# Bluetooth_BM20_Breakout.net
KiCad netlist of a schematic drawn in EAGLE
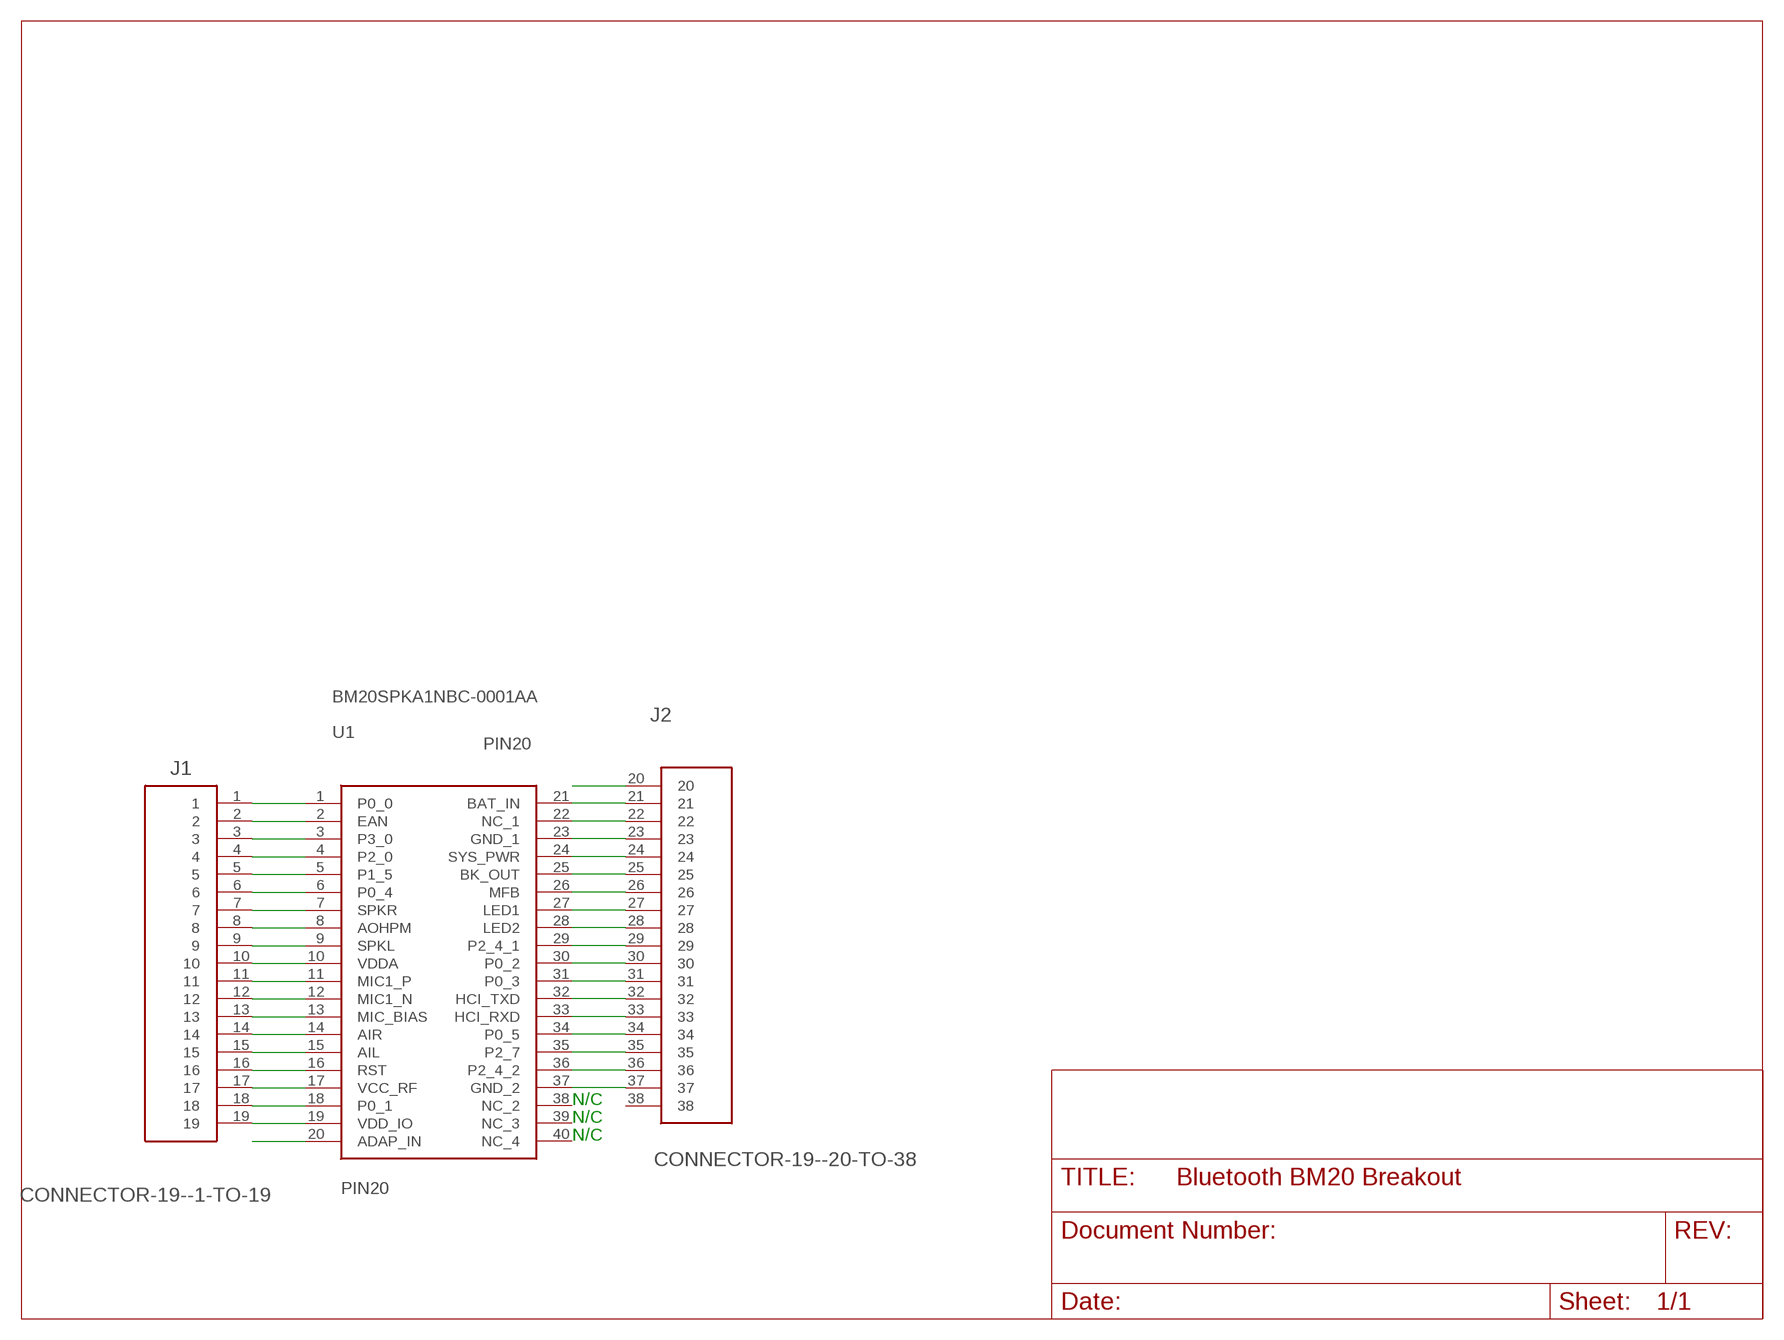
[diagram p0: schematic, sheet 1]

(export (version "E")
  (design (tool "Eeschema 10.0.6"))
  (components
    (comp (ref "J1")
      (value "CONNECTOR-19--1-TO-19")
      (footprint "eagle-import:ESQ-119-XX-XX-S")
      (libsource (lib "eagle-import") (part "CONNECTOR-19--1-TO-19"))
    )
    (comp (ref "J2")
      (value "CONNECTOR-19--20-TO-38")
      (footprint "eagle-import:ESQ-119-XX-XX-S--PIN-1-ROUND")
      (libsource (lib "eagle-import") (part "CONNECTOR-19--20-TO-38"))
    )
    (comp (ref "U1")
      (value "BM20SPKA1NBC-0001AA")
      (footprint "eagle-import:BM20SPKA1NBC0001AA")
      (fields (field (name "MOUSER_PART_NUMBER") "579-SPKA1NBC-0001AA"))
      (libsource (lib "eagle-import") (part "BM20SPKA1NBC-0001AA"))
    )
  )
  (nets
    (net (code "1") (name "/PIN20") (class "Default")
      (node (ref "J2") (pin "20") (pinfunction "20_20") (pintype "bidirectional"))
      (node (ref "U1") (pin "20") (pinfunction "ADAP_IN_20") (pintype "bidirectional"))
    )
    (net (code "2") (name "Net-(U1-AIL)") (class "Default")
      (node (ref "J1") (pin "15") (pinfunction "15_15") (pintype "bidirectional"))
      (node (ref "U1") (pin "15") (pinfunction "AIL_15") (pintype "bidirectional"))
    )
    (net (code "3") (name "Net-(U1-AIR)") (class "Default")
      (node (ref "J1") (pin "14") (pinfunction "14_14") (pintype "bidirectional"))
      (node (ref "U1") (pin "14") (pinfunction "AIR_14") (pintype "bidirectional"))
    )
    (net (code "4") (name "Net-(U1-AOHPM)") (class "Default")
      (node (ref "J1") (pin "8") (pinfunction "8_8") (pintype "bidirectional"))
      (node (ref "U1") (pin "8") (pinfunction "AOHPM_8") (pintype "bidirectional"))
    )
    (net (code "5") (name "Net-(U1-BAT_IN)") (class "Default")
      (node (ref "J2") (pin "21") (pinfunction "21_21") (pintype "bidirectional"))
      (node (ref "U1") (pin "21") (pinfunction "BAT_IN_21") (pintype "bidirectional"))
    )
    (net (code "6") (name "Net-(U1-BK_OUT)") (class "Default")
      (node (ref "J2") (pin "25") (pinfunction "25_25") (pintype "bidirectional"))
      (node (ref "U1") (pin "25") (pinfunction "BK_OUT_25") (pintype "bidirectional"))
    )
    (net (code "7") (name "Net-(U1-EAN)") (class "Default")
      (node (ref "J1") (pin "2") (pinfunction "2_2") (pintype "bidirectional"))
      (node (ref "U1") (pin "2") (pinfunction "EAN_2") (pintype "bidirectional"))
    )
    (net (code "8") (name "Net-(U1-GND_1)") (class "Default")
      (node (ref "J2") (pin "23") (pinfunction "23_23") (pintype "bidirectional"))
      (node (ref "U1") (pin "23") (pinfunction "GND_1_23") (pintype "bidirectional"))
    )
    (net (code "9") (name "Net-(U1-GND_2)") (class "Default")
      (node (ref "J2") (pin "37") (pinfunction "37_37") (pintype "bidirectional"))
      (node (ref "U1") (pin "37") (pinfunction "GND_2_37") (pintype "bidirectional"))
    )
    (net (code "10") (name "Net-(U1-HCI_RXD)") (class "Default")
      (node (ref "J2") (pin "33") (pinfunction "33_33") (pintype "bidirectional"))
      (node (ref "U1") (pin "33") (pinfunction "HCI_RXD_33") (pintype "bidirectional"))
    )
    (net (code "11") (name "Net-(U1-HCI_TXD)") (class "Default")
      (node (ref "J2") (pin "32") (pinfunction "32_32") (pintype "bidirectional"))
      (node (ref "U1") (pin "32") (pinfunction "HCI_TXD_32") (pintype "bidirectional"))
    )
    (net (code "12") (name "Net-(U1-LED1)") (class "Default")
      (node (ref "J2") (pin "27") (pinfunction "27_27") (pintype "bidirectional"))
      (node (ref "U1") (pin "27") (pinfunction "LED1_27") (pintype "bidirectional"))
    )
    (net (code "13") (name "Net-(U1-LED2)") (class "Default")
      (node (ref "J2") (pin "28") (pinfunction "28_28") (pintype "bidirectional"))
      (node (ref "U1") (pin "28") (pinfunction "LED2_28") (pintype "bidirectional"))
    )
    (net (code "14") (name "Net-(U1-MFB)") (class "Default")
      (node (ref "J2") (pin "26") (pinfunction "26_26") (pintype "bidirectional"))
      (node (ref "U1") (pin "26") (pinfunction "MFB_26") (pintype "bidirectional"))
    )
    (net (code "15") (name "Net-(U1-MIC1_N)") (class "Default")
      (node (ref "J1") (pin "12") (pinfunction "12_12") (pintype "bidirectional"))
      (node (ref "U1") (pin "12") (pinfunction "MIC1_N_12") (pintype "bidirectional"))
    )
    (net (code "16") (name "Net-(U1-MIC1_P)") (class "Default")
      (node (ref "J1") (pin "11") (pinfunction "11_11") (pintype "bidirectional"))
      (node (ref "U1") (pin "11") (pinfunction "MIC1_P_11") (pintype "bidirectional"))
    )
    (net (code "17") (name "Net-(U1-MIC_BIAS)") (class "Default")
      (node (ref "J1") (pin "13") (pinfunction "13_13") (pintype "bidirectional"))
      (node (ref "U1") (pin "13") (pinfunction "MIC_BIAS_13") (pintype "bidirectional"))
    )
    (net (code "18") (name "Net-(U1-NC_1)") (class "Default")
      (node (ref "J2") (pin "22") (pinfunction "22_22") (pintype "bidirectional"))
      (node (ref "U1") (pin "22") (pinfunction "NC_1_22") (pintype "bidirectional"))
    )
    (net (code "19") (name "Net-(U1-P0_0)") (class "Default")
      (node (ref "J1") (pin "1") (pinfunction "1_1") (pintype "bidirectional"))
      (node (ref "U1") (pin "1") (pinfunction "P0_0_1") (pintype "bidirectional"))
    )
    (net (code "20") (name "Net-(U1-P0_1)") (class "Default")
      (node (ref "J1") (pin "18") (pinfunction "18_18") (pintype "bidirectional"))
      (node (ref "U1") (pin "18") (pinfunction "P0_1_18") (pintype "bidirectional"))
    )
    (net (code "21") (name "Net-(U1-P0_2)") (class "Default")
      (node (ref "J2") (pin "30") (pinfunction "30_30") (pintype "bidirectional"))
      (node (ref "U1") (pin "30") (pinfunction "P0_2_30") (pintype "bidirectional"))
    )
    (net (code "22") (name "Net-(U1-P0_3)") (class "Default")
      (node (ref "J2") (pin "31") (pinfunction "31_31") (pintype "bidirectional"))
      (node (ref "U1") (pin "31") (pinfunction "P0_3_31") (pintype "bidirectional"))
    )
    (net (code "23") (name "Net-(U1-P0_4)") (class "Default")
      (node (ref "J1") (pin "6") (pinfunction "6_6") (pintype "bidirectional"))
      (node (ref "U1") (pin "6") (pinfunction "P0_4_6") (pintype "bidirectional"))
    )
    (net (code "24") (name "Net-(U1-P0_5)") (class "Default")
      (node (ref "J2") (pin "34") (pinfunction "34_34") (pintype "bidirectional"))
      (node (ref "U1") (pin "34") (pinfunction "P0_5_34") (pintype "bidirectional"))
    )
    (net (code "25") (name "Net-(U1-P1_5)") (class "Default")
      (node (ref "J1") (pin "5") (pinfunction "5_5") (pintype "bidirectional"))
      (node (ref "U1") (pin "5") (pinfunction "P1_5_5") (pintype "bidirectional"))
    )
    (net (code "26") (name "Net-(U1-P2_0)") (class "Default")
      (node (ref "J1") (pin "4") (pinfunction "4_4") (pintype "bidirectional"))
      (node (ref "U1") (pin "4") (pinfunction "P2_0_4") (pintype "bidirectional"))
    )
    (net (code "27") (name "Net-(U1-P2_4_1)") (class "Default")
      (node (ref "J2") (pin "29") (pinfunction "29_29") (pintype "bidirectional"))
      (node (ref "U1") (pin "29") (pinfunction "P2_4_1_29") (pintype "bidirectional"))
    )
    (net (code "28") (name "Net-(U1-P2_4_2)") (class "Default")
      (node (ref "J2") (pin "36") (pinfunction "36_36") (pintype "bidirectional"))
      (node (ref "U1") (pin "36") (pinfunction "P2_4_2_36") (pintype "bidirectional"))
    )
    (net (code "29") (name "Net-(U1-P2_7)") (class "Default")
      (node (ref "J2") (pin "35") (pinfunction "35_35") (pintype "bidirectional"))
      (node (ref "U1") (pin "35") (pinfunction "P2_7_35") (pintype "bidirectional"))
    )
    (net (code "30") (name "Net-(U1-P3_0)") (class "Default")
      (node (ref "J1") (pin "3") (pinfunction "3_3") (pintype "bidirectional"))
      (node (ref "U1") (pin "3") (pinfunction "P3_0_3") (pintype "bidirectional"))
    )
    (net (code "31") (name "Net-(U1-RST)") (class "Default")
      (node (ref "J1") (pin "16") (pinfunction "16_16") (pintype "bidirectional"))
      (node (ref "U1") (pin "16") (pinfunction "RST_16") (pintype "bidirectional"))
    )
    (net (code "32") (name "Net-(U1-SPKL)") (class "Default")
      (node (ref "J1") (pin "9") (pinfunction "9_9") (pintype "bidirectional"))
      (node (ref "U1") (pin "9") (pinfunction "SPKL_9") (pintype "bidirectional"))
    )
    (net (code "33") (name "Net-(U1-SPKR)") (class "Default")
      (node (ref "J1") (pin "7") (pinfunction "7_7") (pintype "bidirectional"))
      (node (ref "U1") (pin "7") (pinfunction "SPKR_7") (pintype "bidirectional"))
    )
    (net (code "34") (name "Net-(U1-SYS_PWR)") (class "Default")
      (node (ref "J2") (pin "24") (pinfunction "24_24") (pintype "bidirectional"))
      (node (ref "U1") (pin "24") (pinfunction "SYS_PWR_24") (pintype "bidirectional"))
    )
    (net (code "35") (name "Net-(U1-VCC_RF)") (class "Default")
      (node (ref "J1") (pin "17") (pinfunction "17_17") (pintype "bidirectional"))
      (node (ref "U1") (pin "17") (pinfunction "VCC_RF_17") (pintype "bidirectional"))
    )
    (net (code "36") (name "Net-(U1-VDDA)") (class "Default")
      (node (ref "J1") (pin "10") (pinfunction "10_10") (pintype "bidirectional"))
      (node (ref "U1") (pin "10") (pinfunction "VDDA_10") (pintype "bidirectional"))
    )
    (net (code "37") (name "Net-(U1-VDD_IO)") (class "Default")
      (node (ref "J1") (pin "19") (pinfunction "19_19") (pintype "bidirectional"))
      (node (ref "U1") (pin "19") (pinfunction "VDD_IO_19") (pintype "bidirectional"))
    )
    (net (code "38") (name "unconnected-(J2-Pad38)") (class "Default")
      (node (ref "J2") (pin "38") (pinfunction "38_38") (pintype "bidirectional"))
    )
    (net (code "39") (name "unconnected-(U1-NC_2-Pad38)") (class "Default")
      (node (ref "U1") (pin "38") (pinfunction "NC_2_38") (pintype "bidirectional"))
    )
    (net (code "40") (name "unconnected-(U1-NC_3-Pad39)") (class "Default")
      (node (ref "U1") (pin "39") (pinfunction "NC_3_39") (pintype "bidirectional"))
    )
    (net (code "41") (name "unconnected-(U1-NC_4-Pad40)") (class "Default")
      (node (ref "U1") (pin "40") (pinfunction "NC_4_40") (pintype "bidirectional"))
    )
  )
)
